# cSLIM-SA_GPS.net
KiCad netlist of a schematic drawn in Altium Designer
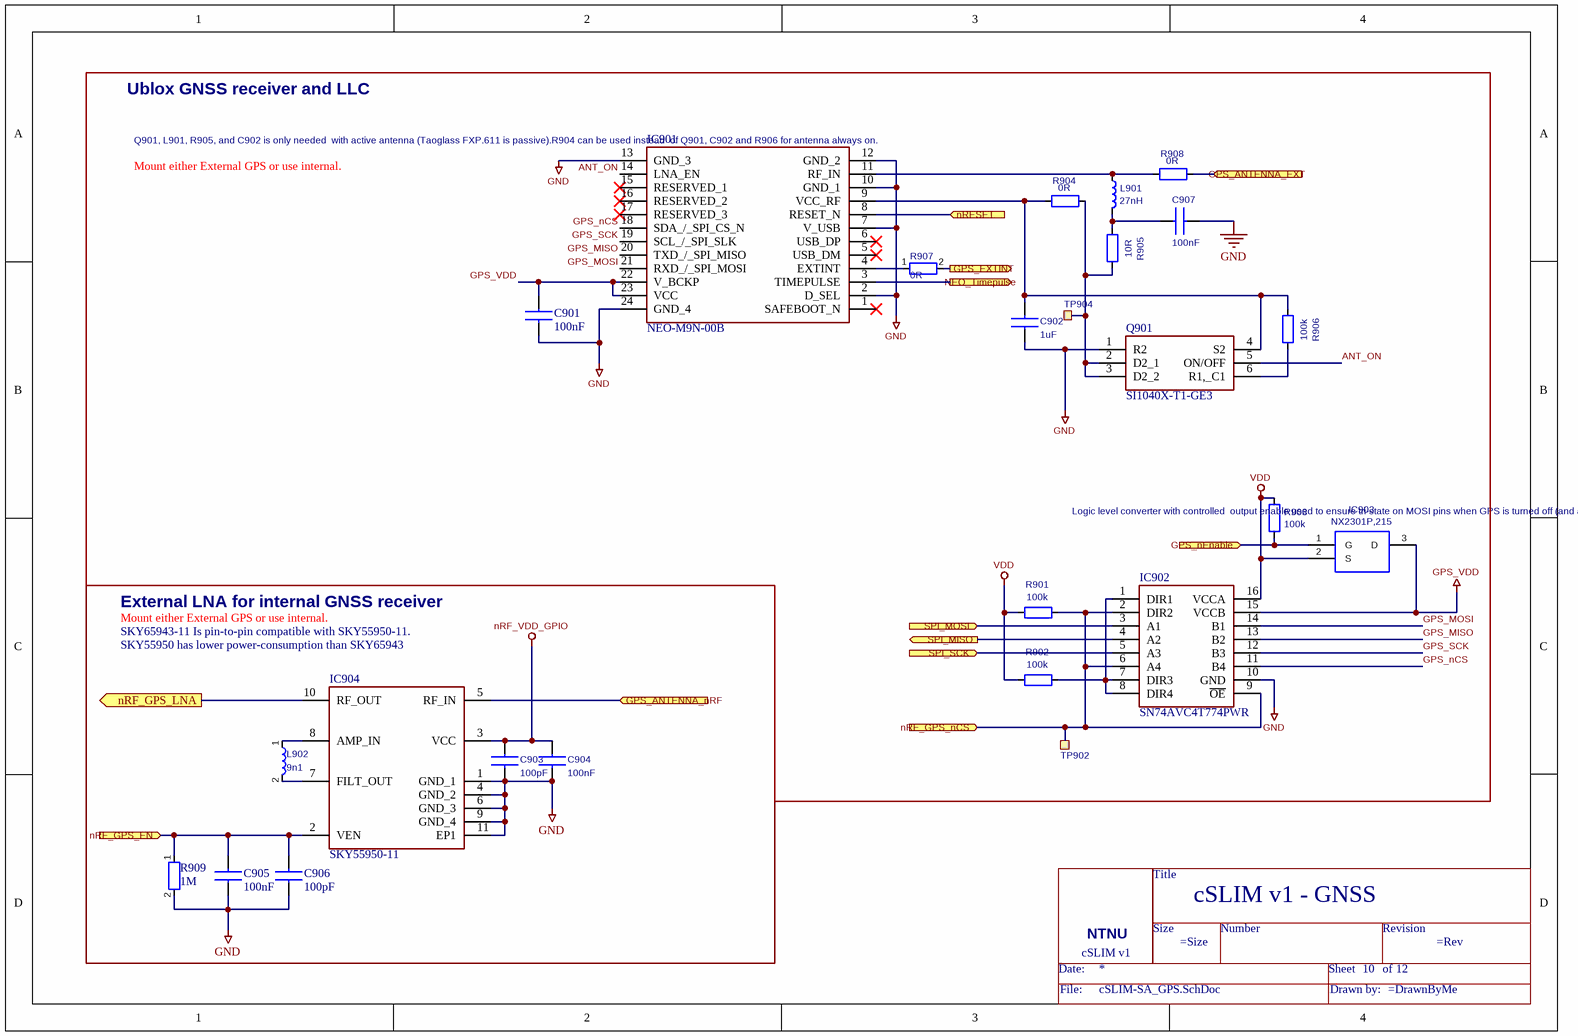
[diagram p0: cSLIM-SA_GPS.SchDoc]

(export (version "E")
  (design (tool "Eeschema 10.0.6"))
  (components
    (comp (ref "C901")
      (value "100nF")
      (footprint "cSLIM-SA:CAPC1608X90N")
      (description "Capacitor")
      (fields
        (field (name "MANUFACTURER_PART_NUMBER") "06033G104ZAT2A")
        (field (name "MOUSER PART NUMBER") "581-06033G104Z")
      )
      (libsource (lib "cSLIM-SA") (part "C"))
    )
    (comp (ref "C902")
      (value "1uF")
      (footprint "cSLIM-SA:CAPC1608X90N")
      (description "Capacitor")
      (fields
        (field (name "MANUFACTURER_PART_NUMBER") "06033G104ZAT2A")
        (field (name "MOUSER PART NUMBER") "581-06033G104Z")
      )
      (libsource (lib "cSLIM-SA") (part "C"))
    )
    (comp (ref "C903")
      (value "100pF")
      (footprint "cSLIM-SA:CAPC1608X90N")
      (description "Capacitor")
      (fields
        (field (name "MANUFACTURER_PART_NUMBER") "06033G104ZAT2A")
        (field (name "MOUSER PART NUMBER") "581-06033G104Z")
      )
      (libsource (lib "cSLIM-SA") (part "C"))
    )
    (comp (ref "C904")
      (value "100nF")
      (footprint "cSLIM-SA:CAPC1608X90N")
      (description "Capacitor")
      (fields
        (field (name "MANUFACTURER_PART_NUMBER") "06033G104ZAT2A")
        (field (name "MOUSER PART NUMBER") "581-06033G104Z")
      )
      (libsource (lib "cSLIM-SA") (part "C"))
    )
    (comp (ref "C905")
      (value "100nF")
      (footprint "cSLIM-SA:CAPC1608X90N")
      (description "Capacitor")
      (fields
        (field (name "MANUFACTURER_PART_NUMBER") "06033G104ZAT2A")
        (field (name "MOUSER PART NUMBER") "581-06033G104Z")
      )
      (libsource (lib "cSLIM-SA") (part "C"))
    )
    (comp (ref "C906")
      (value "100pF")
      (footprint "cSLIM-SA:CAPC1608X90N")
      (description "Capacitor")
      (fields
        (field (name "MANUFACTURER_PART_NUMBER") "06033G104ZAT2A")
        (field (name "MOUSER PART NUMBER") "581-06033G104Z")
      )
      (libsource (lib "cSLIM-SA") (part "C"))
    )
    (comp (ref "C907")
      (value "100nF")
      (footprint "cSLIM-SA:CAPC1608X90N")
      (description "Capacitor")
      (fields
        (field (name "MANUFACTURER_PART_NUMBER") "06033G104ZAT2A")
        (field (name "MOUSER PART NUMBER") "581-06033G104Z")
      )
      (libsource (lib "cSLIM-SA") (part "C"))
    )
    (comp (ref "IC901")
      (value "NEO-M9N-00B")
      (footprint "cSLIM-SA:NEOM9N00B")
      (description "Integrated Circuit")
      (fields (field (name "MOUSER PART NUMBER") "377-NEO-M9N-00B"))
      (libsource (lib "cSLIM-SA") (part "NEO-M9N-00B"))
    )
    (comp (ref "IC902")
      (value "SN74AVC4T774PWR")
      (footprint "cSLIM-SA:SOP65P640X120-16N")
      (description "Integrated Circuit")
      (fields (field (name "MOUSER PART NUMBER") "595-SN74AVC4T774PWR"))
      (libsource (lib "cSLIM-SA") (part "SN74AVC4T774PWR"))
    )
    (comp (ref "IC903")
      (value "NX2301P,215")
      (footprint "SOT95P230X110-3N")
      (fields (field (name "MOUSER PART NUMBER") "771-NX2301P215"))
      (libsource (lib "SamacSys") (part "NX2301P,215"))
    )
    (comp (ref "IC904")
      (value "SKY55950-11")
      (footprint "cSLIM-SA:SKY6594311")
      (description "Integrated Circuit")
      (fields
        (field (name "MANUFACTURER_PART_NUMBER") "SKY65943-11")
        (field (name "MOUSER PART NUMBER") "873-SKY65943-11")
      )
      (libsource (lib "cSLIM-SA") (part "SKY65943-11"))
    )
    (comp (ref "L901") (value "27nH") (footprint "L-1608") (libsource (lib "cSLIM-SA") (part "L")))
    (comp (ref "L902") (value "9n1") (footprint "LQW18AS10NG0CD") (libsource (lib "cSLIM-SA") (part "L_1")))
    (comp (ref "Q901")
      (value "SI1040X-T1-GE3")
      (footprint "cSLIM-SA:SOTFL50P160X60-6N")
      (description "MOSFET (N-Channel)")
      (fields (field (name "MOUSER PART NUMBER") "781-SI1040X-T1-GE3"))
      (libsource (lib "cSLIM-SA") (part "SI1040X-T1-GE3"))
    )
    (comp (ref "R901") (value "100k") (footprint "RESC1608X55N") (libsource (lib "cSLIM-SA") (part "R")))
    (comp (ref "R902") (value "100k") (footprint "RESC1608X55N") (libsource (lib "cSLIM-SA") (part "R")))
    (comp (ref "R903") (value "100k") (footprint "RESC1608X55N") (libsource (lib "") (part "R_2")))
    (comp (ref "R904") (value "0R") (footprint "RESC1608X55N") (libsource (lib "cSLIM-SA") (part "R")))
    (comp (ref "R905") (value "10R") (footprint "RESC1608X55N") (libsource (lib "") (part "R_2")))
    (comp (ref "R906") (value "100k") (footprint "RESC1608X55N") (libsource (lib "") (part "R_2")))
    (comp (ref "R907") (value "0R") (footprint "RESC1608X55N") (libsource (lib "") (part "R_3")))
    (comp (ref "R908") (value "0R") (footprint "RESC1608X55N") (libsource (lib "cSLIM-SA") (part "R")))
    (comp (ref "R909") (value "1M") (footprint "RESC1608X55N") (libsource (lib "") (part "R_1")))
    (comp (ref "TP902")
      (value "~")
      (footprint "cSLIM-SA:TP_SMD_Ø1.0mm")
      (libsource (lib "cSLIM-SA") (part "TP"))
    )
    (comp (ref "TP904") (value "~") (footprint "cSLIM-SA:TP_SMD_Ø1.0mm") (libsource (lib "") (part "TP_1")))
  )
  (nets
    (net (code "1") (name "/ANT_ON") (class "Default")
      (node (ref "IC901") (pin "14") (pinfunction "LNA_EN_14") (pintype "passive"))
      (node (ref "Q901") (pin "5") (pinfunction "ON/OFF_5") (pintype "passive"))
    )
    (net (code "2") (name "/GPS_ANTENNA_EXT") (class "Default")
      (node (ref "R908") (pin "1") (pinfunction "1_1") (pintype "passive"))
    )
    (net (code "3") (name "/GPS_ANTENNA_nRF") (class "Default")
      (node (ref "IC904") (pin "5") (pinfunction "RF_IN_5") (pintype "passive"))
    )
    (net (code "4") (name "/GPS_EXTINT") (class "Default")
      (node (ref "R907") (pin "2") (pinfunction "2_2") (pintype "passive"))
    )
    (net (code "5") (name "/GPS_MISO") (class "Default")
      (node (ref "IC901") (pin "20") (pinfunction "TXD_/_SPI_MISO_20") (pintype "passive"))
      (node (ref "IC902") (pin "13") (pinfunction "B2_13") (pintype "passive"))
    )
    (net (code "6") (name "/GPS_MOSI") (class "Default")
      (node (ref "IC901") (pin "21") (pinfunction "RXD_/_SPI_MOSI_21") (pintype "passive"))
      (node (ref "IC902") (pin "14") (pinfunction "B1_14") (pintype "passive"))
    )
    (net (code "7") (name "/GPS_SCK") (class "Default")
      (node (ref "IC901") (pin "19") (pinfunction "SCL_/_SPI_SLK_19") (pintype "passive"))
      (node (ref "IC902") (pin "12") (pinfunction "B3_12") (pintype "passive"))
    )
    (net (code "8") (name "/GPS_nCS") (class "Default")
      (node (ref "IC901") (pin "18") (pinfunction "SDA_/_SPI_CS_N_18") (pintype "passive"))
      (node (ref "IC902") (pin "11") (pinfunction "B4_11") (pintype "passive"))
    )
    (net (code "9") (name "/GPS_nEnable") (class "Default")
      (node (ref "IC903") (pin "1") (pinfunction "G_1") (pintype "passive"))
      (node (ref "R903") (pin "1") (pinfunction "1_1") (pintype "passive"))
    )
    (net (code "10") (name "/NEO_Timepulse") (class "Default")
      (node (ref "IC901") (pin "3") (pinfunction "TIMEPULSE_3") (pintype "passive"))
    )
    (net (code "11") (name "/SPI_MISO") (class "Default")
      (node (ref "IC902") (pin "4") (pinfunction "A2_4") (pintype "passive"))
    )
    (net (code "12") (name "/SPI_MOSI") (class "Default")
      (node (ref "IC902") (pin "3") (pinfunction "A1_3") (pintype "passive"))
    )
    (net (code "13") (name "/SPI_SCK") (class "Default")
      (node (ref "IC902") (pin "5") (pinfunction "A3_5") (pintype "passive"))
    )
    (net (code "14") (name "/nRESET") (class "Default")
      (node (ref "IC901") (pin "8") (pinfunction "RESET_N_8") (pintype "passive"))
    )
    (net (code "15") (name "/nRF_GPS_EN") (class "Default")
      (node (ref "C905") (pin "2") (pinfunction "2_2") (pintype "passive"))
      (node (ref "C906") (pin "2") (pinfunction "2_2") (pintype "passive"))
      (node (ref "IC904") (pin "2") (pinfunction "VEN_2") (pintype "passive"))
      (node (ref "R909") (pin "1") (pinfunction "1_1") (pintype "passive"))
    )
    (net (code "16") (name "/nRF_GPS_LNA") (class "Default")
      (node (ref "IC904") (pin "10") (pinfunction "RF_OUT_10") (pintype "passive"))
    )
    (net (code "17") (name "/nRF_GPS_nCS") (class "Default")
      (node (ref "IC902") (pin "2") (pinfunction "DIR2_2") (pintype "passive"))
      (node (ref "IC902") (pin "6") (pinfunction "A4_6") (pintype "passive"))
      (node (ref "IC902") (pin "9") (pinfunction "~{OE}_9") (pintype "passive"))
      (node (ref "R901") (pin "1") (pinfunction "1_1") (pintype "passive"))
      (node (ref "TP902") (pin "1") (pinfunction "1_1") (pintype "passive"))
    )
    (net (code "18") (name "GND") (class "Default")
      (node (ref "C901") (pin "2") (pinfunction "2_2") (pintype "passive"))
      (node (ref "C902") (pin "2") (pinfunction "2_2") (pintype "passive"))
      (node (ref "C903") (pin "1") (pinfunction "1_1") (pintype "passive"))
      (node (ref "C904") (pin "1") (pinfunction "1_1") (pintype "passive"))
      (node (ref "C905") (pin "1") (pinfunction "1_1") (pintype "passive"))
      (node (ref "C906") (pin "1") (pinfunction "1_1") (pintype "passive"))
      (node (ref "C907") (pin "2") (pinfunction "2_2") (pintype "passive"))
      (node (ref "IC901") (pin "10") (pinfunction "GND_1_10") (pintype "passive"))
      (node (ref "IC901") (pin "12") (pinfunction "GND_2_12") (pintype "passive"))
      (node (ref "IC901") (pin "13") (pinfunction "GND_3_13") (pintype "passive"))
      (node (ref "IC901") (pin "2") (pinfunction "D_SEL_2") (pintype "passive"))
      (node (ref "IC901") (pin "24") (pinfunction "GND_4_24") (pintype "passive"))
      (node (ref "IC901") (pin "7") (pinfunction "V_USB_7") (pintype "passive"))
      (node (ref "IC902") (pin "10") (pinfunction "GND_10") (pintype "passive"))
      (node (ref "IC904") (pin "1") (pinfunction "GND_1_1") (pintype "passive"))
      (node (ref "IC904") (pin "11") (pinfunction "EP1_11") (pintype "passive"))
      (node (ref "IC904") (pin "4") (pinfunction "GND_2_4") (pintype "passive"))
      (node (ref "IC904") (pin "6") (pinfunction "GND_3_6") (pintype "passive"))
      (node (ref "IC904") (pin "9") (pinfunction "GND_4_9") (pintype "passive"))
      (node (ref "Q901") (pin "1") (pinfunction "R2_1") (pintype "passive"))
      (node (ref "R909") (pin "2") (pinfunction "2_2") (pintype "passive"))
    )
    (net (code "19") (name "GPS_VDD") (class "Default")
      (node (ref "C901") (pin "1") (pinfunction "1_1") (pintype "passive"))
      (node (ref "IC901") (pin "22") (pinfunction "V_BCKP_22") (pintype "passive"))
      (node (ref "IC901") (pin "23") (pinfunction "VCC_23") (pintype "passive"))
      (node (ref "IC902") (pin "15") (pinfunction "VCCB_15") (pintype "passive"))
      (node (ref "IC903") (pin "3") (pinfunction "D_3") (pintype "passive"))
    )
    (net (code "20") (name "Net-(C907-Pad1)") (class "Default")
      (node (ref "C907") (pin "1") (pinfunction "1_1") (pintype "passive"))
      (node (ref "L901") (pin "2") (pinfunction "2_2") (pintype "passive"))
      (node (ref "R905") (pin "2") (pinfunction "2_2") (pintype "passive"))
    )
    (net (code "21") (name "Net-(IC901-EXTINT)") (class "Default")
      (node (ref "IC901") (pin "4") (pinfunction "EXTINT_4") (pintype "passive"))
      (node (ref "R907") (pin "1") (pinfunction "1_1") (pintype "passive"))
    )
    (net (code "22") (name "Net-(IC901-RF_IN)") (class "Default")
      (node (ref "IC901") (pin "11") (pinfunction "RF_IN_11") (pintype "passive"))
      (node (ref "L901") (pin "1") (pinfunction "1_1") (pintype "passive"))
      (node (ref "R908") (pin "2") (pinfunction "2_2") (pintype "passive"))
    )
    (net (code "23") (name "Net-(IC901-VCC_RF)") (class "Default")
      (node (ref "C902") (pin "1") (pinfunction "1_1") (pintype "passive"))
      (node (ref "IC901") (pin "9") (pinfunction "VCC_RF_9") (pintype "passive"))
      (node (ref "Q901") (pin "4") (pinfunction "S2_4") (pintype "passive"))
      (node (ref "R904") (pin "2") (pinfunction "2_2") (pintype "passive"))
      (node (ref "R906") (pin "2") (pinfunction "2_2") (pintype "passive"))
    )
    (net (code "24") (name "Net-(IC902-DIR1)") (class "Default")
      (node (ref "IC902") (pin "1") (pinfunction "DIR1_1") (pintype "passive"))
      (node (ref "IC902") (pin "7") (pinfunction "DIR3_7") (pintype "passive"))
      (node (ref "IC902") (pin "8") (pinfunction "DIR4_8") (pintype "passive"))
      (node (ref "R902") (pin "1") (pinfunction "1_1") (pintype "passive"))
    )
    (net (code "25") (name "Net-(IC904-AMP_IN)") (class "Default")
      (node (ref "IC904") (pin "8") (pinfunction "AMP_IN_8") (pintype "passive"))
      (node (ref "L902") (pin "1") (pinfunction "1_1") (pintype "passive"))
    )
    (net (code "26") (name "Net-(IC904-FILT_OUT)") (class "Default")
      (node (ref "IC904") (pin "7") (pinfunction "FILT_OUT_7") (pintype "passive"))
      (node (ref "L902") (pin "2") (pinfunction "2_2") (pintype "passive"))
    )
    (net (code "27") (name "Net-(Q901-D2_1)") (class "Default")
      (node (ref "Q901") (pin "2") (pinfunction "D2_1_2") (pintype "passive"))
      (node (ref "Q901") (pin "3") (pinfunction "D2_2_3") (pintype "passive"))
      (node (ref "R904") (pin "1") (pinfunction "1_1") (pintype "passive"))
      (node (ref "R905") (pin "1") (pinfunction "1_1") (pintype "passive"))
      (node (ref "TP904") (pin "1") (pinfunction "1_1") (pintype "passive"))
    )
    (net (code "28") (name "Net-(Q901-R1,_C1)") (class "Default")
      (node (ref "Q901") (pin "6") (pinfunction "R1,_C1_6") (pintype "passive"))
      (node (ref "R906") (pin "1") (pinfunction "1_1") (pintype "passive"))
    )
    (net (code "29") (name "VDD") (class "Default")
      (node (ref "IC902") (pin "16") (pinfunction "VCCA_16") (pintype "passive"))
      (node (ref "IC903") (pin "2") (pinfunction "S_2") (pintype "passive"))
      (node (ref "R901") (pin "2") (pinfunction "2_2") (pintype "passive"))
      (node (ref "R902") (pin "2") (pinfunction "2_2") (pintype "passive"))
      (node (ref "R903") (pin "2") (pinfunction "2_2") (pintype "passive"))
    )
    (net (code "30") (name "nRF_VDD_GPIO") (class "Default")
      (node (ref "C903") (pin "2") (pinfunction "2_2") (pintype "passive"))
      (node (ref "C904") (pin "2") (pinfunction "2_2") (pintype "passive"))
      (node (ref "IC904") (pin "3") (pinfunction "VCC_3") (pintype "passive"))
    )
    (net (code "31") (name "unconnected-(IC901-RESERVED_1-Pad15)") (class "Default")
      (node (ref "IC901") (pin "15") (pinfunction "RESERVED_1_15") (pintype "passive+no_connect"))
    )
    (net (code "32") (name "unconnected-(IC901-RESERVED_2-Pad16)") (class "Default")
      (node (ref "IC901") (pin "16") (pinfunction "RESERVED_2_16") (pintype "passive+no_connect"))
    )
    (net (code "33") (name "unconnected-(IC901-RESERVED_3-Pad17)") (class "Default")
      (node (ref "IC901") (pin "17") (pinfunction "RESERVED_3_17") (pintype "passive+no_connect"))
    )
    (net (code "34") (name "unconnected-(IC901-SAFEBOOT_N-Pad1)") (class "Default")
      (node (ref "IC901") (pin "1") (pinfunction "SAFEBOOT_N_1") (pintype "passive+no_connect"))
    )
    (net (code "35") (name "unconnected-(IC901-USB_DM-Pad5)") (class "Default")
      (node (ref "IC901") (pin "5") (pinfunction "USB_DM_5") (pintype "passive+no_connect"))
    )
    (net (code "36") (name "unconnected-(IC901-USB_DP-Pad6)") (class "Default")
      (node (ref "IC901") (pin "6") (pinfunction "USB_DP_6") (pintype "passive+no_connect"))
    )
  )
)
